# Pyr0-Piezo_Orion_Adapter_v1_0_0.net
KiCad netlist of a schematic drawn in EAGLE
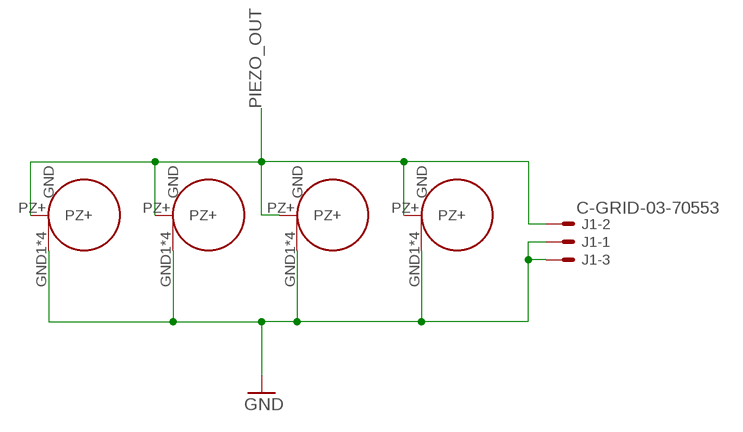
[diagram p0: schematic, sheet 1]

(export (version "E")
  (design (tool "Eeschema 10.0.6"))
  (components
    (comp (ref "J1")
      (value "C-GRID-03-70553")
      (footprint "eagle-import:70553-03")
      (fields (field (name "MF") "MOLEX"))
      (libsource (lib "eagle-import") (part "C-GRID-03-70553"))
    )
    (comp (ref "U$1")
      (value "PIEZO-DISK12MM")
      (footprint "eagle-import:PIEZO-DISK-12MM")
      (libsource (lib "eagle-import") (part "PIEZO-DISK12MM"))
    )
    (comp (ref "U$2")
      (value "PIEZO-DISK12MM")
      (footprint "eagle-import:PIEZO-DISK-12MM")
      (libsource (lib "eagle-import") (part "PIEZO-DISK12MM"))
    )
    (comp (ref "U$3")
      (value "PIEZO-DISK12MM")
      (footprint "eagle-import:PIEZO-DISK-12MM")
      (libsource (lib "eagle-import") (part "PIEZO-DISK12MM"))
    )
    (comp (ref "U$4")
      (value "PIEZO-DISK12MM")
      (footprint "eagle-import:PIEZO-DISK-12MM")
      (libsource (lib "eagle-import") (part "PIEZO-DISK12MM"))
    )
  )
  (nets
    (net (code "1") (name "/PIEZO_OUT") (class "Default")
      (node (ref "J1") (pin "2") (pinfunction "S_2") (pintype "passive"))
      (node (ref "U$1") (pin "PZ+") (pinfunction "PZ+_PZ+") (pintype "bidirectional"))
      (node (ref "U$2") (pin "PZ+") (pinfunction "PZ+_PZ+") (pintype "bidirectional"))
      (node (ref "U$3") (pin "PZ+") (pinfunction "PZ+_PZ+") (pintype "bidirectional"))
      (node (ref "U$4") (pin "PZ+") (pinfunction "PZ+_PZ+") (pintype "bidirectional"))
    )
    (net (code "2") (name "GND") (class "Default")
      (node (ref "J1") (pin "1") (pinfunction "S_1") (pintype "passive"))
      (node (ref "J1") (pin "3") (pinfunction "S_3") (pintype "passive"))
      (node (ref "U$1") (pin "GND1") (pinfunction "GND_GND1") (pintype "passive"))
      (node (ref "U$1") (pin "GND2") (pinfunction "GND_GND2") (pintype "passive"))
      (node (ref "U$1") (pin "GND3") (pinfunction "GND_GND3") (pintype "passive"))
      (node (ref "U$1") (pin "GND4") (pinfunction "GND_GND4") (pintype "passive"))
      (node (ref "U$2") (pin "GND1") (pinfunction "GND_GND1") (pintype "passive"))
      (node (ref "U$2") (pin "GND2") (pinfunction "GND_GND2") (pintype "passive"))
      (node (ref "U$2") (pin "GND3") (pinfunction "GND_GND3") (pintype "passive"))
      (node (ref "U$2") (pin "GND4") (pinfunction "GND_GND4") (pintype "passive"))
      (node (ref "U$3") (pin "GND1") (pinfunction "GND_GND1") (pintype "passive"))
      (node (ref "U$3") (pin "GND2") (pinfunction "GND_GND2") (pintype "passive"))
      (node (ref "U$3") (pin "GND3") (pinfunction "GND_GND3") (pintype "passive"))
      (node (ref "U$3") (pin "GND4") (pinfunction "GND_GND4") (pintype "passive"))
      (node (ref "U$4") (pin "GND1") (pinfunction "GND_GND1") (pintype "passive"))
      (node (ref "U$4") (pin "GND2") (pinfunction "GND_GND2") (pintype "passive"))
      (node (ref "U$4") (pin "GND3") (pinfunction "GND_GND3") (pintype "passive"))
      (node (ref "U$4") (pin "GND4") (pinfunction "GND_GND4") (pintype "passive"))
    )
  )
)
